# star.net
KiCad netlist of a schematic drawn in EAGLE
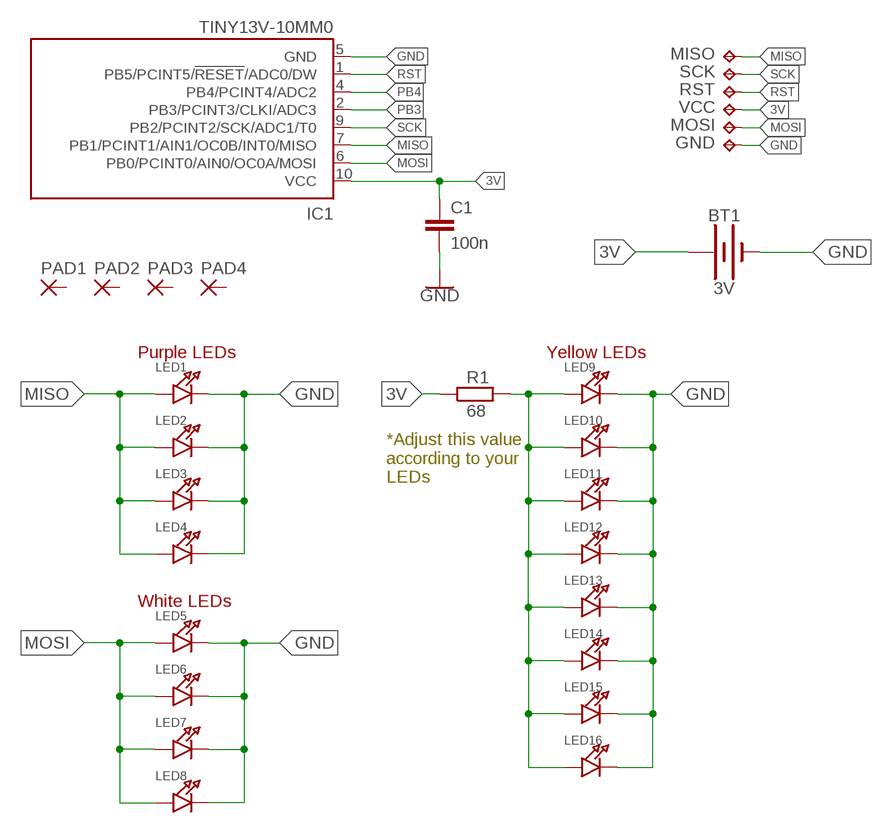
[diagram p0: schematic, sheet 1]

(export (version "E")
  (design (tool "Eeschema 10.0.6"))
  (components
    (comp (ref "BT1")
      (value "3V")
      (footprint "eagle-import:BATTCON_12MM")
      (libsource (lib "eagle-import") (part "BATTERY-12MM_SMD"))
    )
    (comp (ref "C1")
      (value "100n")
      (footprint "eagle-import:C0603K")
      (libsource (lib "eagle-import") (part "C-EUC0603K"))
    )
    (comp (ref "GND")
      (value "TPB1,27")
      (footprint "eagle-import:B1,27")
      (libsource (lib "eagle-import") (part "TPB1,27"))
    )
    (comp (ref "IC1")
      (value "TINY13V-10MM0")
      (footprint "eagle-import:10M1")
      (fields (field (name "MPN") "ATTINY13A-MMU"))
      (libsource (lib "eagle-import") (part "TINY13MM0V-10"))
    )
    (comp (ref "LED1")
      (value "LED0603_NOOUTLINE")
      (footprint "eagle-import:CHIPLED_0603_NOOUTLINE")
      (libsource (lib "eagle-import") (part "LED0603_NOOUTLINE"))
    )
    (comp (ref "LED2")
      (value "LED0603_NOOUTLINE")
      (footprint "eagle-import:CHIPLED_0603_NOOUTLINE")
      (libsource (lib "eagle-import") (part "LED0603_NOOUTLINE"))
    )
    (comp (ref "LED3")
      (value "LED0603_NOOUTLINE")
      (footprint "eagle-import:CHIPLED_0603_NOOUTLINE")
      (libsource (lib "eagle-import") (part "LED0603_NOOUTLINE"))
    )
    (comp (ref "LED4")
      (value "LED0603_NOOUTLINE")
      (footprint "eagle-import:CHIPLED_0603_NOOUTLINE")
      (libsource (lib "eagle-import") (part "LED0603_NOOUTLINE"))
    )
    (comp (ref "LED5")
      (value "LED0603_NOOUTLINE")
      (footprint "eagle-import:CHIPLED_0603_NOOUTLINE")
      (libsource (lib "eagle-import") (part "LED0603_NOOUTLINE"))
    )
    (comp (ref "LED6")
      (value "LED0603_NOOUTLINE")
      (footprint "eagle-import:CHIPLED_0603_NOOUTLINE")
      (libsource (lib "eagle-import") (part "LED0603_NOOUTLINE"))
    )
    (comp (ref "LED7")
      (value "LED0603_NOOUTLINE")
      (footprint "eagle-import:CHIPLED_0603_NOOUTLINE")
      (libsource (lib "eagle-import") (part "LED0603_NOOUTLINE"))
    )
    (comp (ref "LED8")
      (value "LED0603_NOOUTLINE")
      (footprint "eagle-import:CHIPLED_0603_NOOUTLINE")
      (libsource (lib "eagle-import") (part "LED0603_NOOUTLINE"))
    )
    (comp (ref "LED9")
      (value "LED0603_NOOUTLINE")
      (footprint "eagle-import:CHIPLED_0603_NOOUTLINE")
      (libsource (lib "eagle-import") (part "LED0603_NOOUTLINE"))
    )
    (comp (ref "LED10")
      (value "LED0603_NOOUTLINE")
      (footprint "eagle-import:CHIPLED_0603_NOOUTLINE")
      (libsource (lib "eagle-import") (part "LED0603_NOOUTLINE"))
    )
    (comp (ref "LED11")
      (value "LED0603_NOOUTLINE")
      (footprint "eagle-import:CHIPLED_0603_NOOUTLINE")
      (libsource (lib "eagle-import") (part "LED0603_NOOUTLINE"))
    )
    (comp (ref "LED12")
      (value "LED0603_NOOUTLINE")
      (footprint "eagle-import:CHIPLED_0603_NOOUTLINE")
      (libsource (lib "eagle-import") (part "LED0603_NOOUTLINE"))
    )
    (comp (ref "LED13")
      (value "LED0603_NOOUTLINE")
      (footprint "eagle-import:CHIPLED_0603_NOOUTLINE")
      (libsource (lib "eagle-import") (part "LED0603_NOOUTLINE"))
    )
    (comp (ref "LED14")
      (value "LED0603_NOOUTLINE")
      (footprint "eagle-import:CHIPLED_0603_NOOUTLINE")
      (libsource (lib "eagle-import") (part "LED0603_NOOUTLINE"))
    )
    (comp (ref "LED15")
      (value "LED0603_NOOUTLINE")
      (footprint "eagle-import:CHIPLED_0603_NOOUTLINE")
      (libsource (lib "eagle-import") (part "LED0603_NOOUTLINE"))
    )
    (comp (ref "LED16")
      (value "LED0603_NOOUTLINE")
      (footprint "eagle-import:CHIPLED_0603_NOOUTLINE")
      (libsource (lib "eagle-import") (part "LED0603_NOOUTLINE"))
    )
    (comp (ref "MISO")
      (value "TPB1,27")
      (footprint "eagle-import:B1,27")
      (libsource (lib "eagle-import") (part "TPB1,27"))
    )
    (comp (ref "MOSI")
      (value "TPB1,27")
      (footprint "eagle-import:B1,27")
      (libsource (lib "eagle-import") (part "TPB1,27"))
    )
    (comp (ref "PAD1")
      (value "SMD2")
      (footprint "eagle-import:SMD1,27-2,54")
      (libsource (lib "eagle-import") (part "SMD2"))
    )
    (comp (ref "PAD2")
      (value "SMD2")
      (footprint "eagle-import:SMD1,27-2,54")
      (libsource (lib "eagle-import") (part "SMD2"))
    )
    (comp (ref "PAD3")
      (value "SMD2")
      (footprint "eagle-import:SMD1,27-2,54")
      (libsource (lib "eagle-import") (part "SMD2"))
    )
    (comp (ref "PAD4")
      (value "SMD2")
      (footprint "eagle-import:SMD1,27-2,54")
      (libsource (lib "eagle-import") (part "SMD2"))
    )
    (comp (ref "R1")
      (value "68")
      (footprint "eagle-import:R0603")
      (libsource (lib "eagle-import") (part "R-EU_R0603"))
    )
    (comp (ref "RST")
      (value "TPB1,27")
      (footprint "eagle-import:B1,27")
      (libsource (lib "eagle-import") (part "TPB1,27"))
    )
    (comp (ref "SCK")
      (value "TPB1,27")
      (footprint "eagle-import:B1,27")
      (libsource (lib "eagle-import") (part "TPB1,27"))
    )
    (comp (ref "VCC")
      (value "TPB1,27")
      (footprint "eagle-import:B1,27")
      (libsource (lib "eagle-import") (part "TPB1,27"))
    )
  )
  (nets
    (net (code "1") (name "3V") (class "Default")
      (node (ref "BT1") (pin "PWR@2") (pinfunction "+_PWR@2") (pintype "power_in"))
      (node (ref "C1") (pin "1") (pinfunction "1_1") (pintype "passive"))
      (node (ref "IC1") (pin "10") (pinfunction "VCC_10") (pintype "power_in"))
      (node (ref "R1") (pin "1") (pinfunction "1_1") (pintype "passive"))
      (node (ref "VCC") (pin "TP") (pinfunction "TP_TP") (pintype "input"))
    )
    (net (code "2") (name "GND") (class "Default")
      (node (ref "BT1") (pin "GND") (pinfunction "-_GND") (pintype "power_in"))
      (node (ref "C1") (pin "2") (pinfunction "2_2") (pintype "passive"))
      (node (ref "GND") (pin "TP") (pinfunction "TP_TP") (pintype "input"))
      (node (ref "IC1") (pin "5") (pinfunction "GND_5") (pintype "power_in"))
      (node (ref "LED1") (pin "C") (pinfunction "C_C") (pintype "passive"))
      (node (ref "LED10") (pin "C") (pinfunction "C_C") (pintype "passive"))
      (node (ref "LED11") (pin "C") (pinfunction "C_C") (pintype "passive"))
      (node (ref "LED12") (pin "C") (pinfunction "C_C") (pintype "passive"))
      (node (ref "LED13") (pin "C") (pinfunction "C_C") (pintype "passive"))
      (node (ref "LED14") (pin "C") (pinfunction "C_C") (pintype "passive"))
      (node (ref "LED15") (pin "C") (pinfunction "C_C") (pintype "passive"))
      (node (ref "LED16") (pin "C") (pinfunction "C_C") (pintype "passive"))
      (node (ref "LED2") (pin "C") (pinfunction "C_C") (pintype "passive"))
      (node (ref "LED3") (pin "C") (pinfunction "C_C") (pintype "passive"))
      (node (ref "LED4") (pin "C") (pinfunction "C_C") (pintype "passive"))
      (node (ref "LED5") (pin "C") (pinfunction "C_C") (pintype "passive"))
      (node (ref "LED6") (pin "C") (pinfunction "C_C") (pintype "passive"))
      (node (ref "LED7") (pin "C") (pinfunction "C_C") (pintype "passive"))
      (node (ref "LED8") (pin "C") (pinfunction "C_C") (pintype "passive"))
      (node (ref "LED9") (pin "C") (pinfunction "C_C") (pintype "passive"))
    )
    (net (code "3") (name "MISO") (class "Default")
      (node (ref "IC1") (pin "7") (pinfunction "PB1/PCINT1/AIN1/OC0B/INT0/MISO_7") (pintype "bidirectional"))
      (node (ref "LED1") (pin "A") (pinfunction "A_A") (pintype "passive"))
      (node (ref "LED2") (pin "A") (pinfunction "A_A") (pintype "passive"))
      (node (ref "LED3") (pin "A") (pinfunction "A_A") (pintype "passive"))
      (node (ref "LED4") (pin "A") (pinfunction "A_A") (pintype "passive"))
      (node (ref "MISO") (pin "TP") (pinfunction "TP_TP") (pintype "input"))
    )
    (net (code "4") (name "MOSI") (class "Default")
      (node (ref "IC1") (pin "6") (pinfunction "PB0/PCINT0/AIN0/OC0A/MOSI_6") (pintype "bidirectional"))
      (node (ref "LED5") (pin "A") (pinfunction "A_A") (pintype "passive"))
      (node (ref "LED6") (pin "A") (pinfunction "A_A") (pintype "passive"))
      (node (ref "LED7") (pin "A") (pinfunction "A_A") (pintype "passive"))
      (node (ref "LED8") (pin "A") (pinfunction "A_A") (pintype "passive"))
      (node (ref "MOSI") (pin "TP") (pinfunction "TP_TP") (pintype "input"))
    )
    (net (code "5") (name "Net-(LED10-PadA)") (class "Default")
      (node (ref "LED10") (pin "A") (pinfunction "A_A") (pintype "passive"))
      (node (ref "LED11") (pin "A") (pinfunction "A_A") (pintype "passive"))
      (node (ref "LED12") (pin "A") (pinfunction "A_A") (pintype "passive"))
      (node (ref "LED13") (pin "A") (pinfunction "A_A") (pintype "passive"))
      (node (ref "LED14") (pin "A") (pinfunction "A_A") (pintype "passive"))
      (node (ref "LED15") (pin "A") (pinfunction "A_A") (pintype "passive"))
      (node (ref "LED16") (pin "A") (pinfunction "A_A") (pintype "passive"))
      (node (ref "LED9") (pin "A") (pinfunction "A_A") (pintype "passive"))
      (node (ref "R1") (pin "2") (pinfunction "2_2") (pintype "passive"))
    )
    (net (code "6") (name "PB3") (class "Default")
      (node (ref "IC1") (pin "2") (pinfunction "PB3/PCINT3/CLKI/ADC3_2") (pintype "bidirectional"))
    )
    (net (code "7") (name "PB4") (class "Default")
      (node (ref "IC1") (pin "4") (pinfunction "PB4/PCINT4/ADC2_4") (pintype "bidirectional"))
    )
    (net (code "8") (name "RST") (class "Default")
      (node (ref "IC1") (pin "1") (pinfunction "PB5/PCINT5/~{RESET}/ADC0/DW_1") (pintype "bidirectional"))
      (node (ref "RST") (pin "TP") (pinfunction "TP_TP") (pintype "input"))
    )
    (net (code "9") (name "SCK") (class "Default")
      (node (ref "IC1") (pin "9") (pinfunction "PB2/PCINT2/SCK/ADC1/T0_9") (pintype "bidirectional"))
      (node (ref "SCK") (pin "TP") (pinfunction "TP_TP") (pintype "input"))
    )
    (net (code "10") (name "unconnected-(PAD1-P-Pad1)") (class "Default")
      (node (ref "PAD1") (pin "1") (pinfunction "P_1") (pintype "passive"))
    )
    (net (code "11") (name "unconnected-(PAD2-P-Pad1)") (class "Default")
      (node (ref "PAD2") (pin "1") (pinfunction "P_1") (pintype "passive"))
    )
    (net (code "12") (name "unconnected-(PAD3-P-Pad1)") (class "Default")
      (node (ref "PAD3") (pin "1") (pinfunction "P_1") (pintype "passive"))
    )
    (net (code "13") (name "unconnected-(PAD4-P-Pad1)") (class "Default")
      (node (ref "PAD4") (pin "1") (pinfunction "P_1") (pintype "passive"))
    )
  )
)
